# MK_0_3.net
KiCad netlist of a schematic drawn in Altium Designer
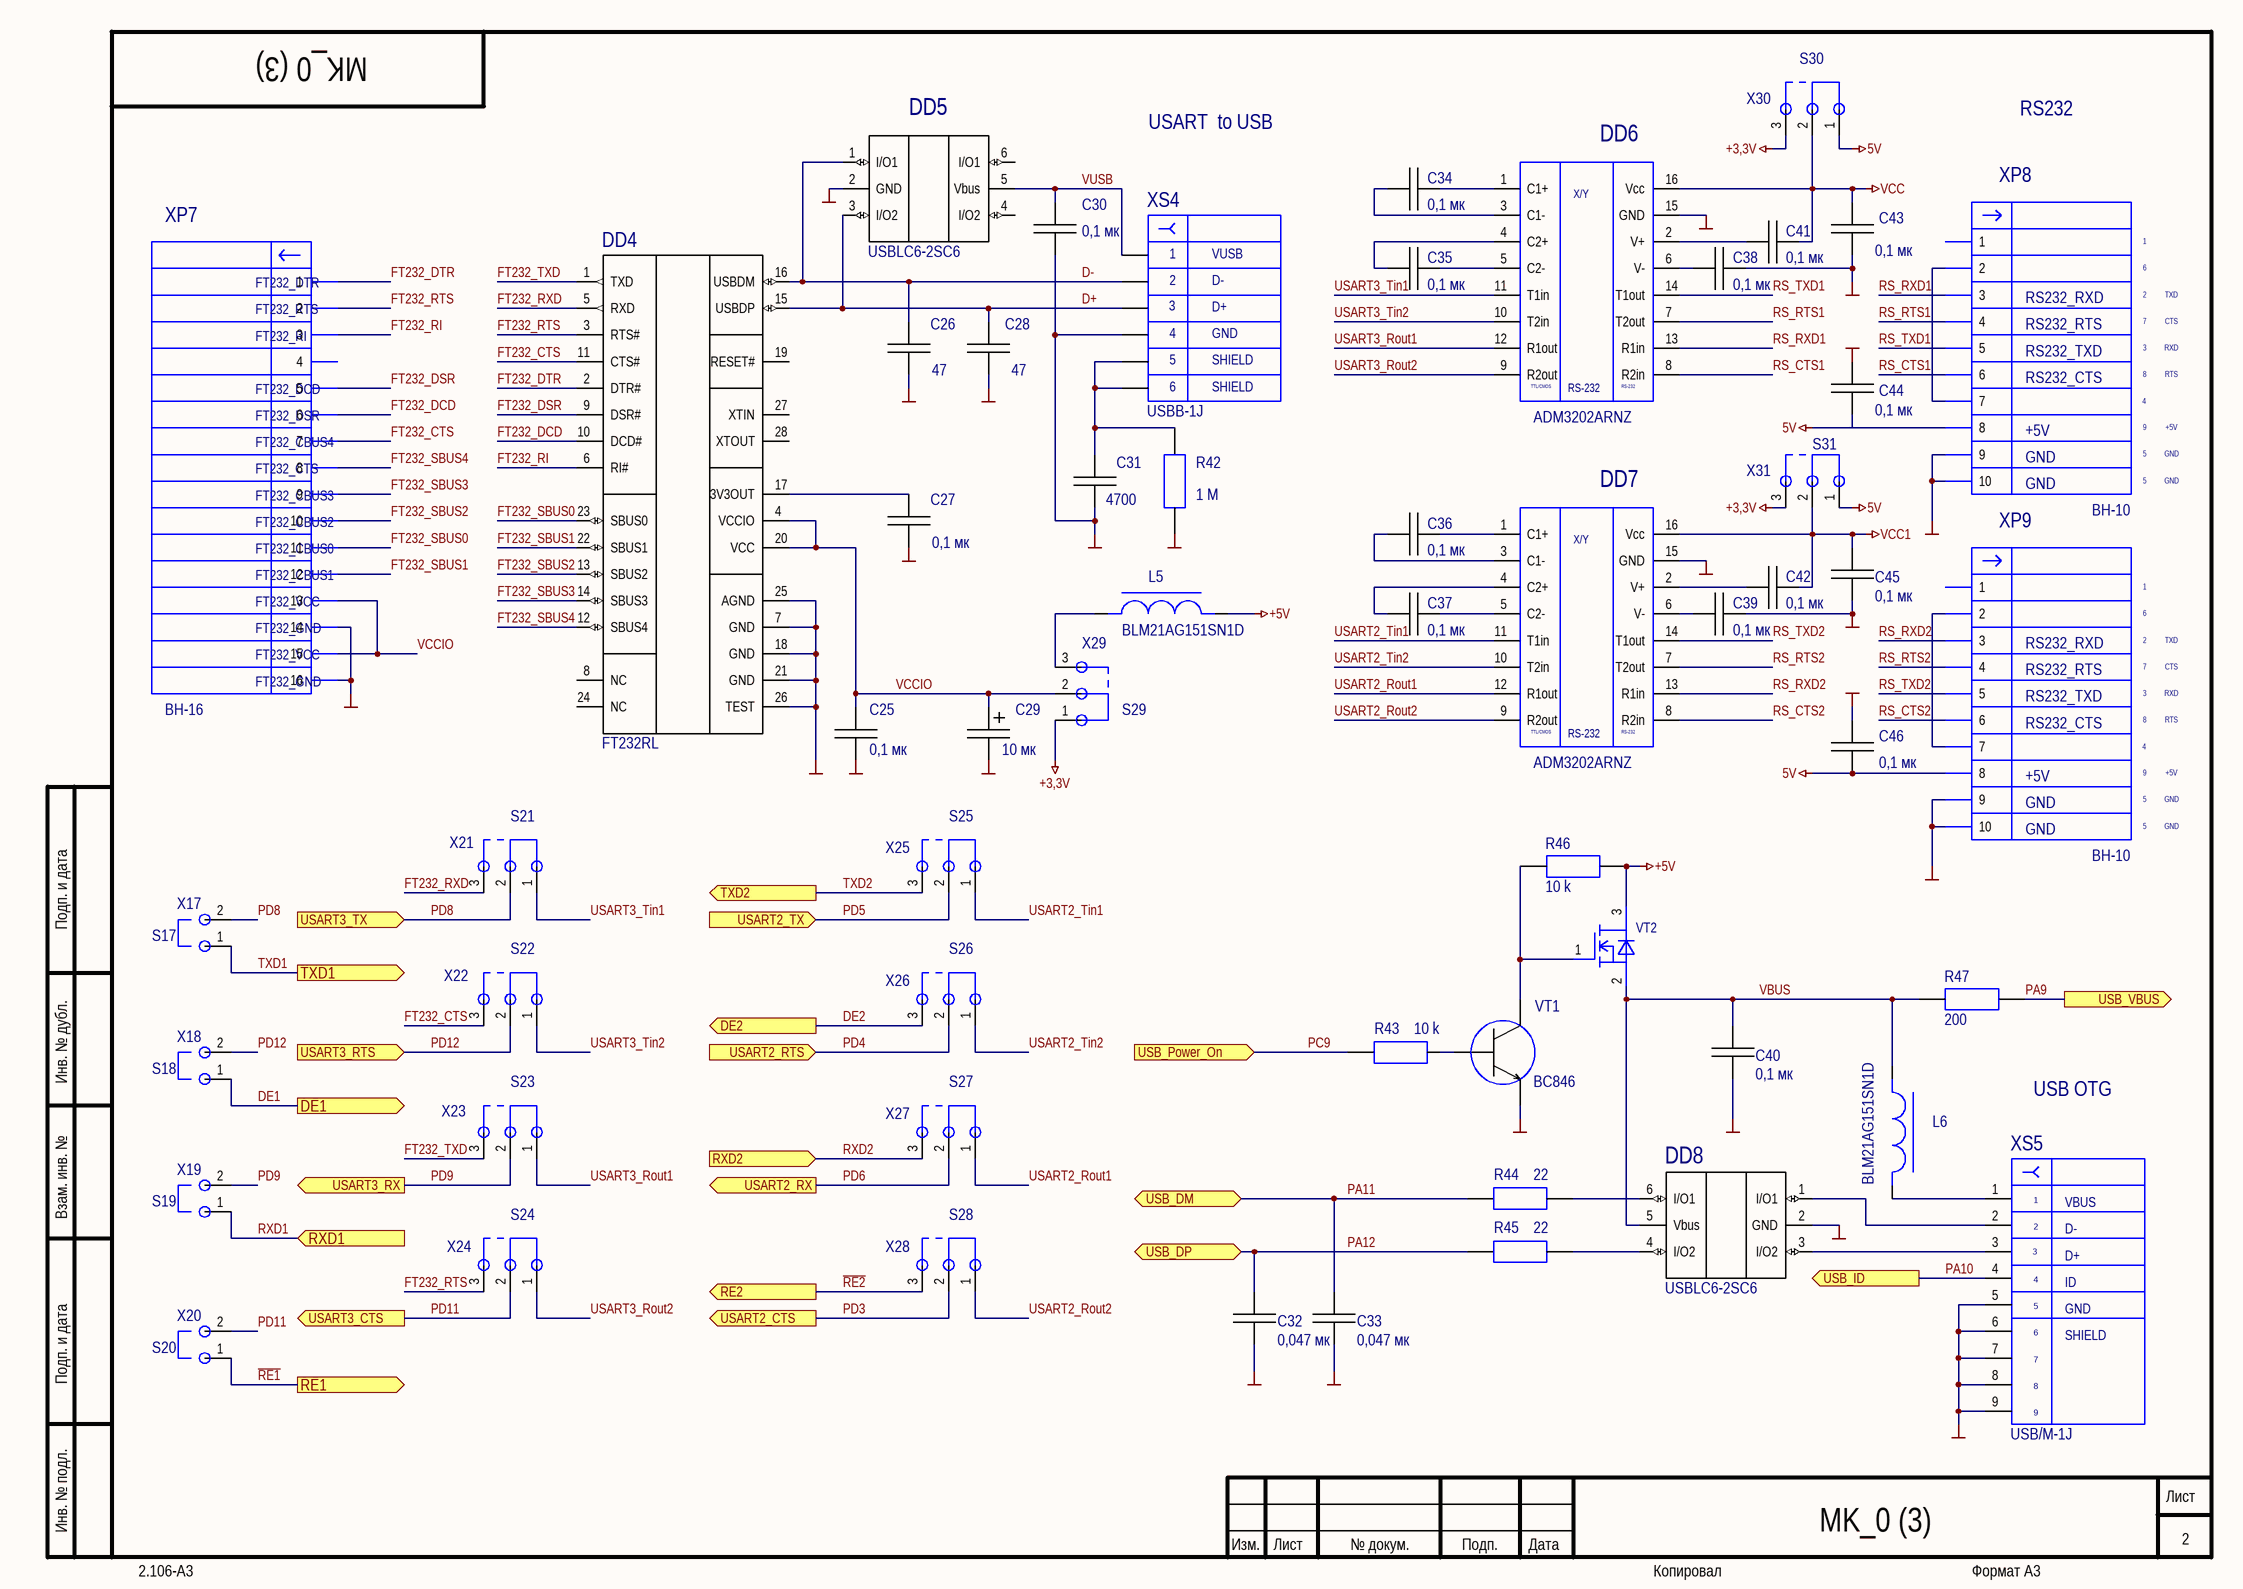
[diagram p0: MK_0 (3).SchDoc]

(export (version "E")
  (design (tool "Eeschema 10.0.6"))
  (components
    (comp (ref "C25")
      (value "0,1 мк")
      (footprint "CAPC_1206")
      (description "Capasitor")
      (fields (field (name "PART NUMBER") "C"))
      (libsource (lib "RLC_GOST") (part "C"))
    )
    (comp (ref "C26")
      (value "47")
      (footprint "CAPC_1206")
      (description "Capasitor")
      (fields (field (name "PART NUMBER") "C"))
      (libsource (lib "RLC_GOST") (part "C"))
    )
    (comp (ref "C27")
      (value "0,1 мк")
      (footprint "CAPC_1206")
      (description "Capasitor")
      (fields (field (name "PART NUMBER") "C"))
      (libsource (lib "RLC_GOST") (part "C"))
    )
    (comp (ref "C28")
      (value "47")
      (footprint "CAPC_1206")
      (description "Capasitor")
      (fields (field (name "PART NUMBER") "C"))
      (libsource (lib "RLC_GOST") (part "C"))
    )
    (comp (ref "C29")
      (value "10 мк")
      (footprint "3216")
      (description "Capasitor_polar")
      (fields (field (name "PART NUMBER") "CapPol"))
      (libsource (lib "RLC_GOST") (part "CapPol"))
    )
    (comp (ref "C30")
      (value "0,1 мк")
      (footprint "CAPC_1206")
      (description "Capasitor")
      (fields (field (name "PART NUMBER") "C"))
      (libsource (lib "RLC_GOST") (part "C"))
    )
    (comp (ref "C31")
      (value "4700")
      (footprint "CAPC_1206")
      (description "Capasitor")
      (fields (field (name "PART NUMBER") "C"))
      (libsource (lib "RLC_GOST") (part "C"))
    )
    (comp (ref "C32")
      (value "0,047 мк")
      (footprint "CAPC_1206")
      (description "Capasitor")
      (fields (field (name "PART NUMBER") "C"))
      (libsource (lib "RLC_GOST") (part "C"))
    )
    (comp (ref "C33")
      (value "0,047 мк")
      (footprint "CAPC_1206")
      (description "Capasitor")
      (fields (field (name "PART NUMBER") "C"))
      (libsource (lib "RLC_GOST") (part "C"))
    )
    (comp (ref "C34")
      (value "0,1 мк")
      (footprint "CAPC_1206")
      (description "Capasitor")
      (fields (field (name "PART NUMBER") "C"))
      (libsource (lib "RLC_GOST") (part "C"))
    )
    (comp (ref "C35")
      (value "0,1 мк")
      (footprint "CAPC_1206")
      (description "Capasitor")
      (fields (field (name "PART NUMBER") "C"))
      (libsource (lib "RLC_GOST") (part "C"))
    )
    (comp (ref "C36")
      (value "0,1 мк")
      (footprint "CAPC_1206")
      (description "Capasitor")
      (fields (field (name "PART NUMBER") "C"))
      (libsource (lib "RLC_GOST") (part "C"))
    )
    (comp (ref "C37")
      (value "0,1 мк")
      (footprint "CAPC_1206")
      (description "Capasitor")
      (fields (field (name "PART NUMBER") "C"))
      (libsource (lib "RLC_GOST") (part "C"))
    )
    (comp (ref "C38")
      (value "0,1 мк")
      (footprint "CAPC_1206")
      (description "Capasitor")
      (fields (field (name "PART NUMBER") "C"))
      (libsource (lib "RLC_GOST") (part "C"))
    )
    (comp (ref "C39")
      (value "0,1 мк")
      (footprint "CAPC_1206")
      (description "Capasitor")
      (fields (field (name "PART NUMBER") "C"))
      (libsource (lib "RLC_GOST") (part "C"))
    )
    (comp (ref "C40")
      (value "0,1 мк")
      (footprint "CAPC_1206")
      (description "Capasitor")
      (fields (field (name "PART NUMBER") "C"))
      (libsource (lib "RLC_GOST") (part "C"))
    )
    (comp (ref "C41")
      (value "0,1 мк")
      (footprint "CAPC_1206")
      (description "Capasitor")
      (fields (field (name "PART NUMBER") "C"))
      (libsource (lib "RLC_GOST") (part "C"))
    )
    (comp (ref "C42")
      (value "0,1 мк")
      (footprint "CAPC_1206")
      (description "Capasitor")
      (fields (field (name "PART NUMBER") "C"))
      (libsource (lib "RLC_GOST") (part "C"))
    )
    (comp (ref "C43")
      (value "0,1 мк")
      (footprint "CAPC_1206")
      (description "Capasitor")
      (fields (field (name "PART NUMBER") "C"))
      (libsource (lib "RLC_GOST") (part "C"))
    )
    (comp (ref "C44")
      (value "0,1 мк")
      (footprint "CAPC_1206")
      (description "Capasitor")
      (fields (field (name "PART NUMBER") "C"))
      (libsource (lib "RLC_GOST") (part "C"))
    )
    (comp (ref "C45")
      (value "0,1 мк")
      (footprint "CAPC_1206")
      (description "Capasitor")
      (fields (field (name "PART NUMBER") "C"))
      (libsource (lib "RLC_GOST") (part "C"))
    )
    (comp (ref "C46")
      (value "0,1 мк")
      (footprint "CAPC_1206")
      (description "Capasitor")
      (fields (field (name "PART NUMBER") "C"))
      (libsource (lib "RLC_GOST") (part "C"))
    )
    (comp (ref "DD4")
      (value "FT232RL")
      (footprint "SSOP28")
      (description "USB to UART interface")
      (libsource (lib "Communication transceiver") (part "FT232RL"))
    )
    (comp (ref "DD5")
      (value "USBLC6-2SC6")
      (footprint "SOT23-6L")
      (description "ESD PROTECTION")
      (libsource (lib "Diod") (part "USBLC6"))
    )
    (comp (ref "DD6")
      (value "ADM3202ARNZ")
      (footprint "SO16")
      (description "CMOS RS232 drivers/receivers")
      (libsource (lib "Communication transceiver") (part "ADM202"))
    )
    (comp (ref "DD7")
      (value "ADM3202ARNZ")
      (footprint "SO16")
      (description "CMOS RS232 drivers/receivers")
      (libsource (lib "Communication transceiver") (part "ADM202"))
    )
    (comp (ref "DD8")
      (value "USBLC6-2SC6")
      (footprint "SOT23-6L")
      (description "ESD PROTECTION")
      (libsource (lib "Diod") (part "USBLC6"))
    )
    (comp (ref "L5")
      (value "BLM21AG151SN1D")
      (footprint "C0805")
      (description "Ferrite bead")
      (libsource (lib "RLC_GOST") (part "B"))
    )
    (comp (ref "L6")
      (value "BLM21AG151SN1D")
      (footprint "C0805")
      (description "Ferrite bead")
      (libsource (lib "RLC_GOST") (part "B"))
    )
    (comp (ref "R42")
      (value "1 M")
      (footprint "SMD_1206")
      (description "Resistor,2 Pin")
      (libsource (lib "RLC_GOST") (part "R_Gost"))
    )
    (comp (ref "R43")
      (value "10 k")
      (footprint "SMD_1206")
      (description "Resistor,2 Pin")
      (libsource (lib "RLC_GOST") (part "R_Gost"))
    )
    (comp (ref "R44")
      (value "22")
      (footprint "SMD_1206")
      (description "Resistor,2 Pin")
      (libsource (lib "RLC_GOST") (part "R_Gost"))
    )
    (comp (ref "R45")
      (value "22")
      (footprint "SMD_1206")
      (description "Resistor,2 Pin")
      (libsource (lib "RLC_GOST") (part "R_Gost"))
    )
    (comp (ref "R46")
      (value "10 k")
      (footprint "SMD_1206")
      (description "Resistor,2 Pin")
      (libsource (lib "RLC_GOST") (part "R_Gost"))
    )
    (comp (ref "R47")
      (value "200")
      (footprint "SMD_1206")
      (description "Resistor,2 Pin")
      (libsource (lib "RLC_GOST") (part "R_Gost"))
    )
    (comp (ref "VT1")
      (value "BC846")
      (footprint "SOT23")
      (description "Transistor NPN Generic")
      (libsource (lib "Transistor") (part "BC846"))
    )
    (comp (ref "VT2")
      (value "IRLML2502")
      (footprint "SOT23")
      (libsource (lib "Transistor") (part "IRLML2502"))
    )
    (comp (ref "X17")
      (value "PLS-02")
      (footprint "PLS-2")
      (fields (field (name "JAMPER") "S17"))
      (libsource (lib "Connectors") (part "J2"))
    )
    (comp (ref "X18")
      (value "PLS-02")
      (footprint "PLS-2")
      (fields (field (name "JAMPER") "S18"))
      (libsource (lib "Connectors") (part "J2"))
    )
    (comp (ref "X19")
      (value "PLS-02")
      (footprint "PLS-2")
      (fields (field (name "JAMPER") "S19"))
      (libsource (lib "Connectors") (part "J2"))
    )
    (comp (ref "X20")
      (value "PLS-02")
      (footprint "PLS-2")
      (fields (field (name "JAMPER") "S20"))
      (libsource (lib "Connectors") (part "J2"))
    )
    (comp (ref "X21")
      (value "PLS-03")
      (footprint "PLS-3")
      (fields (field (name "JAMPER") "S21"))
      (libsource (lib "Connectors") (part "J3"))
    )
    (comp (ref "X22")
      (value "PLS-03")
      (footprint "PLS-3")
      (fields (field (name "JAMPER") "S22"))
      (libsource (lib "Connectors") (part "J3"))
    )
    (comp (ref "X23")
      (value "PLS-03")
      (footprint "PLS-3")
      (fields (field (name "JAMPER") "S23"))
      (libsource (lib "Connectors") (part "J3"))
    )
    (comp (ref "X24")
      (value "PLS-03")
      (footprint "PLS-3")
      (fields (field (name "JAMPER") "S24"))
      (libsource (lib "Connectors") (part "J3"))
    )
    (comp (ref "X25")
      (value "PLS-03")
      (footprint "PLS-3")
      (fields (field (name "JAMPER") "S25"))
      (libsource (lib "Connectors") (part "J3"))
    )
    (comp (ref "X26")
      (value "PLS-03")
      (footprint "PLS-3")
      (fields (field (name "JAMPER") "S26"))
      (libsource (lib "Connectors") (part "J3"))
    )
    (comp (ref "X27")
      (value "PLS-03")
      (footprint "PLS-3")
      (fields (field (name "JAMPER") "S27"))
      (libsource (lib "Connectors") (part "J3"))
    )
    (comp (ref "X28")
      (value "PLS-03")
      (footprint "PLS-3")
      (fields (field (name "JAMPER") "S28"))
      (libsource (lib "Connectors") (part "J3"))
    )
    (comp (ref "X29")
      (value "PLS-03")
      (footprint "PLS-3")
      (fields (field (name "JAMPER") "S29"))
      (libsource (lib "Connectors") (part "J3"))
    )
    (comp (ref "X30")
      (value "PLS-03")
      (footprint "PLS-3")
      (fields (field (name "JAMPER") "S30"))
      (libsource (lib "Connectors") (part "J3"))
    )
    (comp (ref "X31")
      (value "PLS-03")
      (footprint "PLS-3")
      (fields (field (name "JAMPER") "S31"))
      (libsource (lib "Connectors") (part "J3"))
    )
    (comp (ref "XP7") (value "BH-16") (footprint "PLD-16") (libsource (lib "Connectors") (part "BH-16")))
    (comp (ref "XP8") (value "BH-10") (footprint "PLD-10") (libsource (lib "Connectors") (part "BH-10")))
    (comp (ref "XP9") (value "BH-10") (footprint "PLD-10") (libsource (lib "Connectors") (part "BH-10")))
    (comp (ref "XS4") (value "USBB-1J") (footprint "USBB-1J") (libsource (lib "Connectors") (part "USBB-1J")))
    (comp (ref "XS5")
      (value "USB/M-1J")
      (footprint "MINIUSB")
      (description "9 pin connector, USB mini")
      (libsource (lib "Connectors") (part "USB/M-1J"))
    )
  )
  (nets
    (net (code "1") (name "+3,3V") (class "Default")
      (node (ref "X29") (pin "1") (pinfunction "1_1") (pintype "passive"))
      (node (ref "X30") (pin "3") (pinfunction "3_3") (pintype "passive"))
      (node (ref "X31") (pin "3") (pinfunction "3_3") (pintype "passive"))
    )
    (net (code "2") (name "+5V") (class "Default")
      (node (ref "L5") (pin "2") (pinfunction "2_2") (pintype "passive"))
      (node (ref "R46") (pin "2") (pinfunction "2_2") (pintype "passive"))
      (node (ref "VT2") (pin "3") (pinfunction "D_3") (pintype "passive"))
    )
    (net (code "3") (name "/D+") (class "Default")
      (node (ref "C28") (pin "2") (pinfunction "2_2") (pintype "passive"))
      (node (ref "DD4") (pin "15") (pinfunction "USBDP_15") (pintype "bidirectional"))
      (node (ref "DD5") (pin "3") (pinfunction "I/O2_3") (pintype "bidirectional"))
      (node (ref "XS4") (pin "3") (pintype "passive"))
    )
    (net (code "4") (name "/D-") (class "Default")
      (node (ref "C26") (pin "2") (pinfunction "2_2") (pintype "passive"))
      (node (ref "DD4") (pin "16") (pinfunction "USBDM_16") (pintype "bidirectional"))
      (node (ref "DD5") (pin "1") (pinfunction "I/O1_1") (pintype "bidirectional"))
      (node (ref "XS4") (pin "2") (pintype "passive"))
    )
    (net (code "5") (name "/DE1") (class "Default")
      (node (ref "X18") (pin "1") (pinfunction "1_1") (pintype "passive"))
    )
    (net (code "6") (name "/DE2") (class "Default")
      (node (ref "X26") (pin "3") (pinfunction "3_3") (pintype "passive"))
    )
    (net (code "7") (name "/FT232_CTS") (class "Default")
      (node (ref "DD4") (pin "11") (pinfunction "CTS#_11") (pintype "passive"))
      (node (ref "X22") (pin "3") (pinfunction "3_3") (pintype "passive"))
      (node (ref "XP7") (pin "7") (pinfunction "7_7") (pintype "passive"))
    )
    (net (code "8") (name "/FT232_DCD") (class "Default")
      (node (ref "DD4") (pin "10") (pinfunction "DCD#_10") (pintype "passive"))
      (node (ref "XP7") (pin "6") (pinfunction "6_6") (pintype "passive"))
    )
    (net (code "9") (name "/FT232_DSR") (class "Default")
      (node (ref "DD4") (pin "9") (pinfunction "DSR#_9") (pintype "passive"))
      (node (ref "XP7") (pin "5") (pinfunction "5_5") (pintype "passive"))
    )
    (net (code "10") (name "/FT232_DTR") (class "Default")
      (node (ref "DD4") (pin "2") (pinfunction "DTR#_2") (pintype "passive"))
      (node (ref "XP7") (pin "1") (pinfunction "1_1") (pintype "passive"))
    )
    (net (code "11") (name "/FT232_RI") (class "Default")
      (node (ref "DD4") (pin "6") (pinfunction "RI#_6") (pintype "passive"))
      (node (ref "XP7") (pin "3") (pinfunction "3_3") (pintype "passive"))
    )
    (net (code "12") (name "/FT232_RTS") (class "Default")
      (node (ref "DD4") (pin "3") (pinfunction "RTS#_3") (pintype "passive"))
      (node (ref "X24") (pin "3") (pinfunction "3_3") (pintype "passive"))
      (node (ref "XP7") (pin "2") (pinfunction "2_2") (pintype "passive"))
    )
    (net (code "13") (name "/FT232_RXD") (class "Default")
      (node (ref "DD4") (pin "5") (pinfunction "RXD_5") (pintype "output"))
      (node (ref "X21") (pin "3") (pinfunction "3_3") (pintype "passive"))
    )
    (net (code "14") (name "/FT232_SBUS0") (class "Default")
      (node (ref "DD4") (pin "23") (pinfunction "SBUS0_23") (pintype "bidirectional"))
      (node (ref "XP7") (pin "11") (pinfunction "11_11") (pintype "passive"))
    )
    (net (code "15") (name "/FT232_SBUS1") (class "Default")
      (node (ref "DD4") (pin "22") (pinfunction "SBUS1_22") (pintype "bidirectional"))
      (node (ref "XP7") (pin "12") (pinfunction "12_12") (pintype "passive"))
    )
    (net (code "16") (name "/FT232_SBUS2") (class "Default")
      (node (ref "DD4") (pin "13") (pinfunction "SBUS2_13") (pintype "bidirectional"))
      (node (ref "XP7") (pin "10") (pinfunction "10_10") (pintype "passive"))
    )
    (net (code "17") (name "/FT232_SBUS3") (class "Default")
      (node (ref "DD4") (pin "14") (pinfunction "SBUS3_14") (pintype "bidirectional"))
      (node (ref "XP7") (pin "9") (pinfunction "9_9") (pintype "passive"))
    )
    (net (code "18") (name "/FT232_SBUS4") (class "Default")
      (node (ref "DD4") (pin "12") (pinfunction "SBUS4_12") (pintype "bidirectional"))
      (node (ref "XP7") (pin "8") (pinfunction "8_8") (pintype "passive"))
    )
    (net (code "19") (name "/FT232_TXD") (class "Default")
      (node (ref "DD4") (pin "1") (pinfunction "TXD_1") (pintype "output"))
      (node (ref "X23") (pin "3") (pinfunction "3_3") (pintype "passive"))
    )
    (net (code "20") (name "/PA9") (class "Default")
      (node (ref "R47") (pin "2") (pinfunction "2_2") (pintype "passive"))
    )
    (net (code "21") (name "/PA10") (class "Default") (node (ref "XS5") (pin "4") (pintype "passive")))
    (net (code "22") (name "/PA11") (class "Default")
      (node (ref "C33") (pin "2") (pinfunction "2_2") (pintype "passive"))
      (node (ref "R44") (pin "2") (pinfunction "2_2") (pintype "passive"))
    )
    (net (code "23") (name "/PA12") (class "Default")
      (node (ref "C32") (pin "2") (pinfunction "2_2") (pintype "passive"))
      (node (ref "R45") (pin "2") (pinfunction "2_2") (pintype "passive"))
    )
    (net (code "24") (name "/PC9") (class "Default")
      (node (ref "R43") (pin "2") (pinfunction "2_2") (pintype "passive"))
    )
    (net (code "25") (name "/PD3") (class "Default")
      (node (ref "X28") (pin "2") (pinfunction "2_2") (pintype "passive"))
    )
    (net (code "26") (name "/PD4") (class "Default")
      (node (ref "X26") (pin "2") (pinfunction "2_2") (pintype "passive"))
    )
    (net (code "27") (name "/PD5") (class "Default")
      (node (ref "X25") (pin "2") (pinfunction "2_2") (pintype "passive"))
    )
    (net (code "28") (name "/PD6") (class "Default")
      (node (ref "X27") (pin "2") (pinfunction "2_2") (pintype "passive"))
    )
    (net (code "29") (name "/PD8") (class "Default")
      (node (ref "X17") (pin "2") (pinfunction "2_2") (pintype "passive"))
      (node (ref "X21") (pin "2") (pinfunction "2_2") (pintype "passive"))
    )
    (net (code "30") (name "/PD9") (class "Default")
      (node (ref "X19") (pin "2") (pinfunction "2_2") (pintype "passive"))
      (node (ref "X23") (pin "2") (pinfunction "2_2") (pintype "passive"))
    )
    (net (code "31") (name "/PD11") (class "Default")
      (node (ref "X20") (pin "2") (pinfunction "2_2") (pintype "passive"))
      (node (ref "X24") (pin "2") (pinfunction "2_2") (pintype "passive"))
    )
    (net (code "32") (name "/PD12") (class "Default")
      (node (ref "X18") (pin "2") (pinfunction "2_2") (pintype "passive"))
      (node (ref "X22") (pin "2") (pinfunction "2_2") (pintype "passive"))
    )
    (net (code "33") (name "/RE1") (class "Default")
      (node (ref "X20") (pin "1") (pinfunction "1_1") (pintype "passive"))
    )
    (net (code "34") (name "/RE2") (class "Default")
      (node (ref "X28") (pin "3") (pinfunction "3_3") (pintype "passive"))
    )
    (net (code "35") (name "/RS_CTS1") (class "Default")
      (node (ref "DD6") (pin "8") (pinfunction "R2in_8") (pintype "passive"))
      (node (ref "XP8") (pin "6") (pinfunction "6_6") (pintype "passive"))
    )
    (net (code "36") (name "/RS_CTS2") (class "Default")
      (node (ref "DD7") (pin "8") (pinfunction "R2in_8") (pintype "passive"))
      (node (ref "XP9") (pin "6") (pinfunction "6_6") (pintype "passive"))
    )
    (net (code "37") (name "/RS_RTS1") (class "Default")
      (node (ref "DD6") (pin "7") (pinfunction "T2out_7") (pintype "passive"))
      (node (ref "XP8") (pin "4") (pinfunction "4_4") (pintype "passive"))
    )
    (net (code "38") (name "/RS_RTS2") (class "Default")
      (node (ref "DD7") (pin "7") (pinfunction "T2out_7") (pintype "passive"))
      (node (ref "XP9") (pin "4") (pinfunction "4_4") (pintype "passive"))
    )
    (net (code "39") (name "/RS_RXD1") (class "Default")
      (node (ref "DD6") (pin "13") (pinfunction "R1in_13") (pintype "passive"))
      (node (ref "XP8") (pin "3") (pinfunction "3_3") (pintype "passive"))
    )
    (net (code "40") (name "/RS_RXD2") (class "Default")
      (node (ref "DD7") (pin "13") (pinfunction "R1in_13") (pintype "passive"))
      (node (ref "XP9") (pin "3") (pinfunction "3_3") (pintype "passive"))
    )
    (net (code "41") (name "/RS_TXD1") (class "Default")
      (node (ref "DD6") (pin "14") (pinfunction "T1out_14") (pintype "passive"))
      (node (ref "XP8") (pin "5") (pinfunction "5_5") (pintype "passive"))
    )
    (net (code "42") (name "/RS_TXD2") (class "Default")
      (node (ref "DD7") (pin "14") (pinfunction "T1out_14") (pintype "passive"))
      (node (ref "XP9") (pin "5") (pinfunction "5_5") (pintype "passive"))
    )
    (net (code "43") (name "/RXD1") (class "Default")
      (node (ref "X19") (pin "1") (pinfunction "1_1") (pintype "passive"))
    )
    (net (code "44") (name "/RXD2") (class "Default")
      (node (ref "X27") (pin "3") (pinfunction "3_3") (pintype "passive"))
    )
    (net (code "45") (name "/TXD1") (class "Default")
      (node (ref "X17") (pin "1") (pinfunction "1_1") (pintype "passive"))
    )
    (net (code "46") (name "/TXD2") (class "Default")
      (node (ref "X25") (pin "3") (pinfunction "3_3") (pintype "passive"))
    )
    (net (code "47") (name "/USART2_Rout1") (class "Default")
      (node (ref "DD7") (pin "12") (pinfunction "R1out_12") (pintype "passive"))
      (node (ref "X27") (pin "1") (pinfunction "1_1") (pintype "passive"))
    )
    (net (code "48") (name "/USART2_Rout2") (class "Default")
      (node (ref "DD7") (pin "9") (pinfunction "R2out_9") (pintype "passive"))
      (node (ref "X28") (pin "1") (pinfunction "1_1") (pintype "passive"))
    )
    (net (code "49") (name "/USART2_Tin1") (class "Default")
      (node (ref "DD7") (pin "11") (pinfunction "T1in_11") (pintype "passive"))
      (node (ref "X25") (pin "1") (pinfunction "1_1") (pintype "passive"))
    )
    (net (code "50") (name "/USART2_Tin2") (class "Default")
      (node (ref "DD7") (pin "10") (pinfunction "T2in_10") (pintype "passive"))
      (node (ref "X26") (pin "1") (pinfunction "1_1") (pintype "passive"))
    )
    (net (code "51") (name "/USART3_Rout1") (class "Default")
      (node (ref "DD6") (pin "12") (pinfunction "R1out_12") (pintype "passive"))
      (node (ref "X23") (pin "1") (pinfunction "1_1") (pintype "passive"))
    )
    (net (code "52") (name "/USART3_Rout2") (class "Default")
      (node (ref "DD6") (pin "9") (pinfunction "R2out_9") (pintype "passive"))
      (node (ref "X24") (pin "1") (pinfunction "1_1") (pintype "passive"))
    )
    (net (code "53") (name "/USART3_Tin1") (class "Default")
      (node (ref "DD6") (pin "11") (pinfunction "T1in_11") (pintype "passive"))
      (node (ref "X21") (pin "1") (pinfunction "1_1") (pintype "passive"))
    )
    (net (code "54") (name "/USART3_Tin2") (class "Default")
      (node (ref "DD6") (pin "10") (pinfunction "T2in_10") (pintype "passive"))
      (node (ref "X22") (pin "1") (pinfunction "1_1") (pintype "passive"))
    )
    (net (code "55") (name "/VBUS") (class "Default")
      (node (ref "C40") (pin "2") (pinfunction "2_2") (pintype "passive"))
      (node (ref "DD8") (pin "5") (pinfunction "Vbus_5") (pintype "power_in"))
      (node (ref "L6") (pin "1") (pinfunction "1_1") (pintype "passive"))
      (node (ref "R47") (pin "1") (pinfunction "1_1") (pintype "passive"))
      (node (ref "VT2") (pin "2") (pinfunction "S_2") (pintype "passive"))
    )
    (net (code "56") (name "/VCCIO") (class "Default")
      (node (ref "C25") (pin "2") (pinfunction "2_2") (pintype "passive"))
      (node (ref "C29") (pin "1") (pinfunction "+_1") (pintype "passive"))
      (node (ref "DD4") (pin "20") (pinfunction "VCC_20") (pintype "power_in"))
      (node (ref "DD4") (pin "4") (pinfunction "VCCIO_4") (pintype "power_in"))
      (node (ref "X29") (pin "2") (pinfunction "2_2") (pintype "passive"))
      (node (ref "XP7") (pin "13") (pinfunction "13_13") (pintype "passive"))
      (node (ref "XP7") (pin "15") (pinfunction "15_15") (pintype "passive"))
    )
    (net (code "57") (name "/VUSB") (class "Default")
      (node (ref "C30") (pin "2") (pinfunction "2_2") (pintype "passive"))
      (node (ref "DD5") (pin "5") (pinfunction "Vbus_5") (pintype "power_in"))
      (node (ref "XS4") (pin "1") (pintype "passive"))
    )
    (net (code "58") (name "5V") (class "Default")
      (node (ref "C44") (pin "1") (pinfunction "1_1") (pintype "passive"))
      (node (ref "C46") (pin "1") (pinfunction "1_1") (pintype "passive"))
      (node (ref "X30") (pin "1") (pinfunction "1_1") (pintype "passive"))
      (node (ref "X31") (pin "1") (pinfunction "1_1") (pintype "passive"))
      (node (ref "XP8") (pin "8") (pinfunction "8_8") (pintype "passive"))
      (node (ref "XP9") (pin "8") (pinfunction "8_8") (pintype "passive"))
    )
    (net (code "59") (name "GND") (class "Default")
      (node (ref "C25") (pin "1") (pinfunction "1_1") (pintype "passive"))
      (node (ref "C26") (pin "1") (pinfunction "1_1") (pintype "passive"))
      (node (ref "C27") (pin "1") (pinfunction "1_1") (pintype "passive"))
      (node (ref "C28") (pin "1") (pinfunction "1_1") (pintype "passive"))
      (node (ref "C29") (pin "2") (pinfunction "-_2") (pintype "passive"))
      (node (ref "C30") (pin "1") (pinfunction "1_1") (pintype "passive"))
      (node (ref "C31") (pin "1") (pinfunction "1_1") (pintype "passive"))
      (node (ref "C32") (pin "1") (pinfunction "1_1") (pintype "passive"))
      (node (ref "C33") (pin "1") (pinfunction "1_1") (pintype "passive"))
      (node (ref "C38") (pin "2") (pinfunction "2_2") (pintype "passive"))
      (node (ref "C39") (pin "2") (pinfunction "2_2") (pintype "passive"))
      (node (ref "C40") (pin "1") (pinfunction "1_1") (pintype "passive"))
      (node (ref "C43") (pin "1") (pinfunction "1_1") (pintype "passive"))
      (node (ref "C44") (pin "2") (pinfunction "2_2") (pintype "passive"))
      (node (ref "C45") (pin "1") (pinfunction "1_1") (pintype "passive"))
      (node (ref "C46") (pin "2") (pinfunction "2_2") (pintype "passive"))
      (node (ref "DD4") (pin "18") (pinfunction "GND_18") (pintype "power_in"))
      (node (ref "DD4") (pin "21") (pinfunction "GND_21") (pintype "power_in"))
      (node (ref "DD4") (pin "25") (pinfunction "AGND_25") (pintype "power_in"))
      (node (ref "DD4") (pin "26") (pinfunction "TEST_26") (pintype "passive"))
      (node (ref "DD4") (pin "7") (pinfunction "GND_7") (pintype "power_in"))
      (node (ref "DD5") (pin "2") (pinfunction "GND_2") (pintype "power_in"))
      (node (ref "DD6") (pin "15") (pinfunction "GND_15") (pintype "passive"))
      (node (ref "DD7") (pin "15") (pinfunction "GND_15") (pintype "passive"))
      (node (ref "DD8") (pin "2") (pinfunction "GND_2") (pintype "power_in"))
      (node (ref "R42") (pin "1") (pinfunction "1_1") (pintype "passive"))
      (node (ref "VT1") (pin "2") (pinfunction "E_2") (pintype "passive"))
      (node (ref "XP7") (pin "14") (pinfunction "14_14") (pintype "passive"))
      (node (ref "XP7") (pin "16") (pinfunction "16_16") (pintype "passive"))
      (node (ref "XP8") (pin "10") (pinfunction "10_10") (pintype "passive"))
      (node (ref "XP8") (pin "9") (pinfunction "9_9") (pintype "passive"))
      (node (ref "XP9") (pin "10") (pinfunction "10_10") (pintype "passive"))
      (node (ref "XP9") (pin "9") (pinfunction "9_9") (pintype "passive"))
      (node (ref "XS4") (pin "4") (pintype "passive"))
      (node (ref "XS5") (pin "5") (pintype "passive"))
      (node (ref "XS5") (pin "6") (pintype "passive"))
      (node (ref "XS5") (pin "7") (pintype "passive"))
      (node (ref "XS5") (pin "8") (pintype "passive"))
      (node (ref "XS5") (pin "9") (pintype "passive"))
    )
    (net (code "60") (name "Net-(C31-Pad2)") (class "Default")
      (node (ref "C31") (pin "2") (pinfunction "2_2") (pintype "passive"))
      (node (ref "R42") (pin "2") (pinfunction "2_2") (pintype "passive"))
      (node (ref "XS4") (pin "5") (pintype "passive"))
      (node (ref "XS4") (pin "6") (pintype "passive"))
    )
    (net (code "61") (name "Net-(DD4-3V3OUT)") (class "Default")
      (node (ref "C27") (pin "2") (pinfunction "2_2") (pintype "passive"))
      (node (ref "DD4") (pin "17") (pinfunction "3V3OUT_17") (pintype "power_in"))
    )
    (net (code "62") (name "Net-(DD6-C1+)") (class "Default")
      (node (ref "C34") (pin "2") (pinfunction "2_2") (pintype "passive"))
      (node (ref "DD6") (pin "1") (pinfunction "C1+_1") (pintype "passive"))
    )
    (net (code "63") (name "Net-(DD6-C1-)") (class "Default")
      (node (ref "C34") (pin "1") (pinfunction "1_1") (pintype "passive"))
      (node (ref "DD6") (pin "3") (pinfunction "C1-_3") (pintype "passive"))
    )
    (net (code "64") (name "Net-(DD6-C2+)") (class "Default")
      (node (ref "C35") (pin "1") (pinfunction "1_1") (pintype "passive"))
      (node (ref "DD6") (pin "4") (pinfunction "C2+_4") (pintype "passive"))
    )
    (net (code "65") (name "Net-(DD6-C2-)") (class "Default")
      (node (ref "C35") (pin "2") (pinfunction "2_2") (pintype "passive"))
      (node (ref "DD6") (pin "5") (pinfunction "C2-_5") (pintype "passive"))
    )
    (net (code "66") (name "Net-(DD6-V+)") (class "Default")
      (node (ref "C41") (pin "1") (pinfunction "1_1") (pintype "passive"))
      (node (ref "DD6") (pin "2") (pinfunction "V+_2") (pintype "passive"))
    )
    (net (code "67") (name "Net-(DD6-V-)") (class "Default")
      (node (ref "C38") (pin "1") (pinfunction "1_1") (pintype "passive"))
      (node (ref "DD6") (pin "6") (pinfunction "V-_6") (pintype "passive"))
    )
    (net (code "68") (name "Net-(DD7-C1+)") (class "Default")
      (node (ref "C36") (pin "2") (pinfunction "2_2") (pintype "passive"))
      (node (ref "DD7") (pin "1") (pinfunction "C1+_1") (pintype "passive"))
    )
    (net (code "69") (name "Net-(DD7-C1-)") (class "Default")
      (node (ref "C36") (pin "1") (pinfunction "1_1") (pintype "passive"))
      (node (ref "DD7") (pin "3") (pinfunction "C1-_3") (pintype "passive"))
    )
    (net (code "70") (name "Net-(DD7-C2+)") (class "Default")
      (node (ref "C37") (pin "1") (pinfunction "1_1") (pintype "passive"))
      (node (ref "DD7") (pin "4") (pinfunction "C2+_4") (pintype "passive"))
    )
    (net (code "71") (name "Net-(DD7-C2-)") (class "Default")
      (node (ref "C37") (pin "2") (pinfunction "2_2") (pintype "passive"))
      (node (ref "DD7") (pin "5") (pinfunction "C2-_5") (pintype "passive"))
    )
    (net (code "72") (name "Net-(DD7-V+)") (class "Default")
      (node (ref "C42") (pin "1") (pinfunction "1_1") (pintype "passive"))
      (node (ref "DD7") (pin "2") (pinfunction "V+_2") (pintype "passive"))
    )
    (net (code "73") (name "Net-(DD7-V-)") (class "Default")
      (node (ref "C39") (pin "1") (pinfunction "1_1") (pintype "passive"))
      (node (ref "DD7") (pin "6") (pinfunction "V-_6") (pintype "passive"))
    )
    (net (code "74") (name "Net-(DD8-I{slash}O1-Pad1)") (class "Default")
      (node (ref "DD8") (pin "1") (pinfunction "I/O1_1") (pintype "bidirectional"))
      (node (ref "XS5") (pin "2") (pintype "passive"))
    )
    (net (code "75") (name "Net-(DD8-I{slash}O1-Pad6)") (class "Default")
      (node (ref "DD8") (pin "6") (pinfunction "I/O1_6") (pintype "bidirectional"))
      (node (ref "R44") (pin "1") (pinfunction "1_1") (pintype "passive"))
    )
    (net (code "76") (name "Net-(DD8-I{slash}O2-Pad3)") (class "Default")
      (node (ref "DD8") (pin "3") (pinfunction "I/O2_3") (pintype "bidirectional"))
      (node (ref "XS5") (pin "3") (pintype "passive"))
    )
    (net (code "77") (name "Net-(DD8-I{slash}O2-Pad4)") (class "Default")
      (node (ref "DD8") (pin "4") (pinfunction "I/O2_4") (pintype "bidirectional"))
      (node (ref "R45") (pin "1") (pinfunction "1_1") (pintype "passive"))
    )
    (net (code "78") (name "Net-(L5-Pad1)") (class "Default")
      (node (ref "L5") (pin "1") (pinfunction "1_1") (pintype "passive"))
      (node (ref "X29") (pin "3") (pinfunction "3_3") (pintype "passive"))
    )
    (net (code "79") (name "Net-(L6-Pad2)") (class "Default")
      (node (ref "L6") (pin "2") (pinfunction "2_2") (pintype "passive"))
      (node (ref "XS5") (pin "1") (pintype "passive"))
    )
    (net (code "80") (name "Net-(VT1-B)") (class "Default")
      (node (ref "R43") (pin "1") (pinfunction "1_1") (pintype "passive"))
      (node (ref "VT1") (pin "1") (pinfunction "B_1") (pintype "passive"))
    )
    (net (code "81") (name "Net-(VT1-K)") (class "Default")
      (node (ref "R46") (pin "1") (pinfunction "1_1") (pintype "passive"))
      (node (ref "VT1") (pin "3") (pinfunction "K_3") (pintype "passive"))
      (node (ref "VT2") (pin "1") (pinfunction "G_1") (pintype "passive"))
    )
    (net (code "82") (name "Net-(XP8-Pad2)") (class "Default")
      (node (ref "XP8") (pin "2") (pinfunction "2_2") (pintype "passive"))
      (node (ref "XP8") (pin "7") (pinfunction "7_7") (pintype "passive"))
    )
    (net (code "83") (name "Net-(XP9-Pad2)") (class "Default")
      (node (ref "XP9") (pin "2") (pinfunction "2_2") (pintype "passive"))
      (node (ref "XP9") (pin "7") (pinfunction "7_7") (pintype "passive"))
    )
    (net (code "84") (name "VCC") (class "Default")
      (node (ref "C41") (pin "2") (pinfunction "2_2") (pintype "passive"))
      (node (ref "C43") (pin "2") (pinfunction "2_2") (pintype "passive"))
      (node (ref "DD6") (pin "16") (pinfunction "Vcc_16") (pintype "passive"))
      (node (ref "X30") (pin "2") (pinfunction "2_2") (pintype "passive"))
    )
    (net (code "85") (name "VCC1") (class "Default")
      (node (ref "C42") (pin "2") (pinfunction "2_2") (pintype "passive"))
      (node (ref "C45") (pin "2") (pinfunction "2_2") (pintype "passive"))
      (node (ref "DD7") (pin "16") (pinfunction "Vcc_16") (pintype "passive"))
      (node (ref "X31") (pin "2") (pinfunction "2_2") (pintype "passive"))
    )
    (net (code "86") (name "unconnected-(DD4-NC-Pad8)") (class "Default")
      (node (ref "DD4") (pin "8") (pinfunction "NC_8") (pintype "passive"))
    )
    (net (code "87") (name "unconnected-(DD4-NC-Pad24)") (class "Default")
      (node (ref "DD4") (pin "24") (pinfunction "NC_24") (pintype "passive"))
    )
    (net (code "88") (name "unconnected-(DD4-RESET#-Pad19)") (class "Default")
      (node (ref "DD4") (pin "19") (pinfunction "RESET#_19") (pintype "passive"))
    )
    (net (code "89") (name "unconnected-(DD4-XTIN-Pad27)") (class "Default")
      (node (ref "DD4") (pin "27") (pinfunction "XTIN_27") (pintype "passive"))
    )
    (net (code "90") (name "unconnected-(DD4-XTOUT-Pad28)") (class "Default")
      (node (ref "DD4") (pin "28") (pinfunction "XTOUT_28") (pintype "passive"))
    )
    (net (code "91") (name "unconnected-(DD5-I{slash}O1-Pad6)") (class "Default")
      (node (ref "DD5") (pin "6") (pinfunction "I/O1_6") (pintype "bidirectional"))
    )
    (net (code "92") (name "unconnected-(DD5-I{slash}O2-Pad4)") (class "Default")
      (node (ref "DD5") (pin "4") (pinfunction "I/O2_4") (pintype "bidirectional"))
    )
    (net (code "93") (name "unconnected-(XP7-Pad4)") (class "Default")
      (node (ref "XP7") (pin "4") (pinfunction "4_4") (pintype "passive"))
    )
    (net (code "94") (name "unconnected-(XP8-Pad1)") (class "Default")
      (node (ref "XP8") (pin "1") (pinfunction "1_1") (pintype "passive"))
    )
    (net (code "95") (name "unconnected-(XP9-Pad1)") (class "Default")
      (node (ref "XP9") (pin "1") (pinfunction "1_1") (pintype "passive"))
    )
  )
)
